# BV10011_ControlIOConnector.net
KiCad netlist of a schematic drawn in Altium Designer
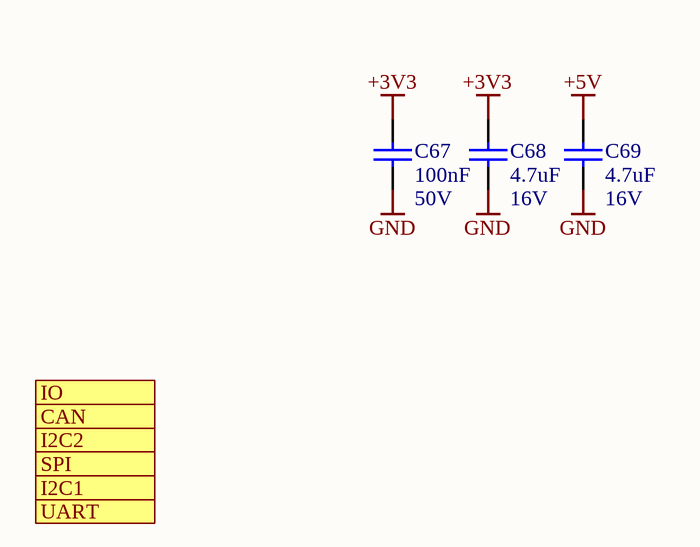
[diagram p0: BV10011_ControlIOConnector.SchDoc]

(export (version "E")
  (design (tool "Eeschema 10.0.6"))
  (components
    (comp (ref "C67")
      (value "100nF")
      (footprint "C-0805")
      (description "Capacitor, 100nF, 50V,  X7R")
      (fields (field (name "VOLTAGE RATING") "50V"))
      (libsource (lib "AR_Capacitors_Ceramic") (part "100nF/0805/CER/50V"))
    )
    (comp (ref "C68")
      (value "4.7uF")
      (footprint "C-0805")
      (description "Capacitor, 4.7uF, 16V, X7R")
      (fields (field (name "VOLTAGE RATING") "16V"))
      (libsource (lib "AR_Capacitors_Ceramic") (part "4.7uF/0805/CER/16V"))
    )
    (comp (ref "C69")
      (value "4.7uF")
      (footprint "C-0805")
      (description "Capacitor, 4.7uF, 16V, X7R")
      (fields (field (name "VOLTAGE RATING") "16V"))
      (libsource (lib "AR_Capacitors_Ceramic") (part "4.7uF/0805/CER/16V"))
    )
  )
  (nets
    (net (code "7") (name "+3V3") (class "Default")
      (node (ref "C67") (pin "2") (pinfunction "2_2") (pintype "passive"))
      (node (ref "C68") (pin "2") (pinfunction "2_2") (pintype "passive"))
    )
    (net (code "8") (name "+5V") (class "Default")
      (node (ref "C69") (pin "2") (pinfunction "2_2") (pintype "passive"))
    )
    (net (code "15") (name "GND") (class "Default")
      (node (ref "C67") (pin "1") (pinfunction "1_1") (pintype "passive"))
      (node (ref "C68") (pin "1") (pinfunction "1_1") (pintype "passive"))
      (node (ref "C69") (pin "1") (pinfunction "1_1") (pintype "passive"))
    )
  )
)
